# murdock_top_v3.net
KiCad netlist of a schematic drawn in EAGLE
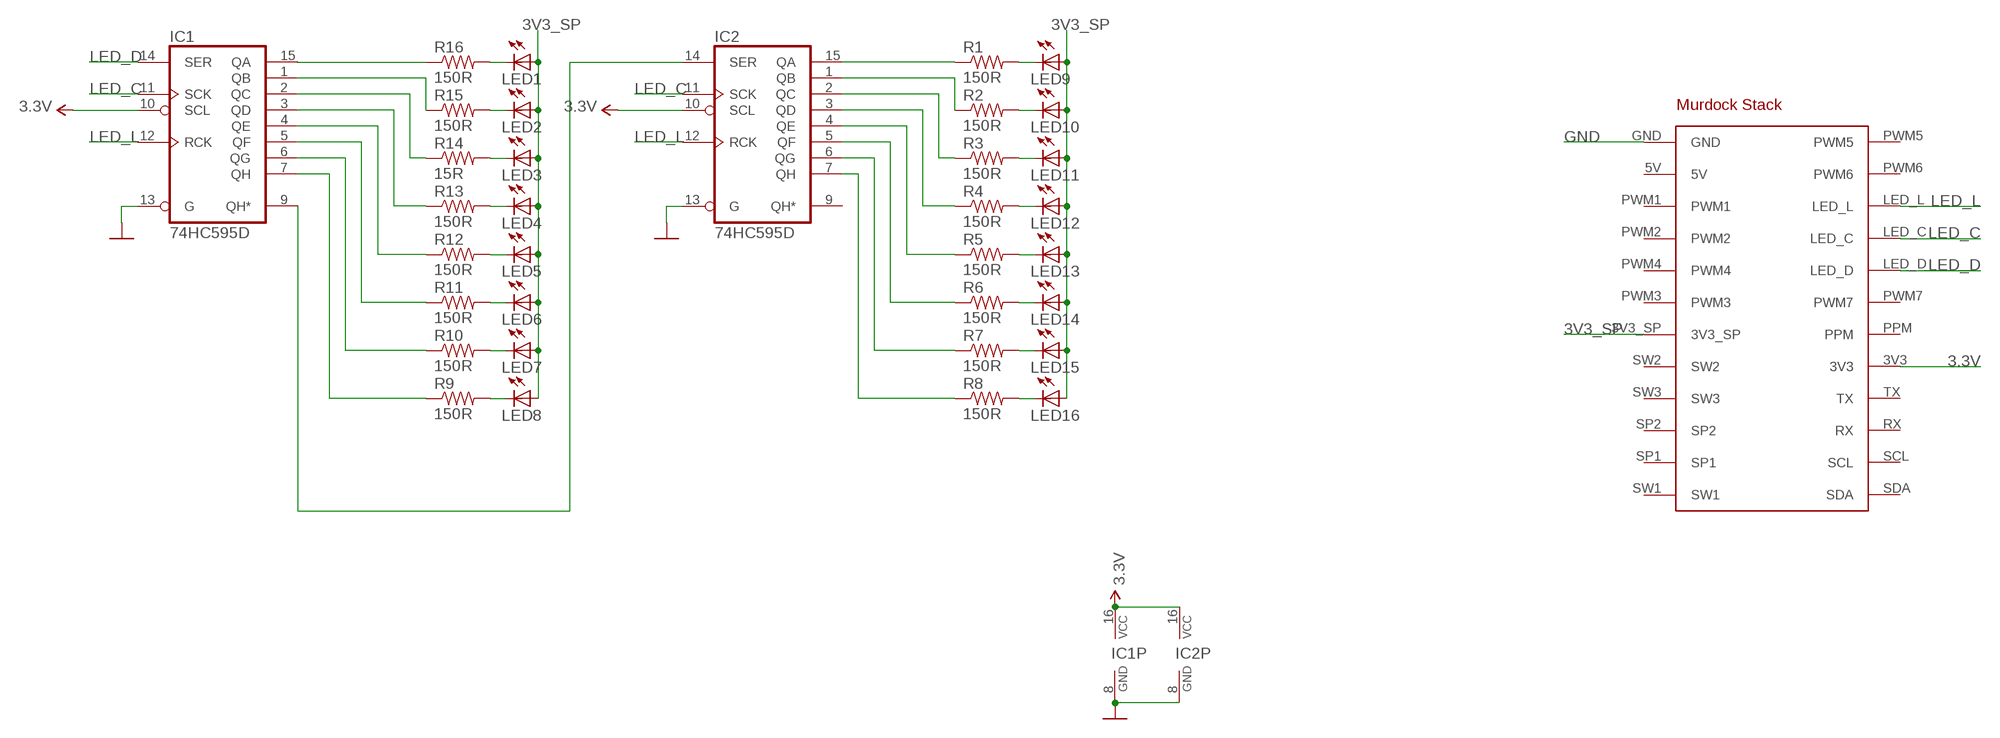
[diagram p0: schematic, sheet 1]

(export (version "E")
  (design (tool "Eeschema 10.0.6"))
  (components
    (comp (ref "IC1")
      (value "74HC595D")
      (footprint "eagle-import:SO16")
      (libsource (lib "eagle-import") (part "74595DHC"))
    )
    (comp (ref "IC2")
      (value "74HC595D")
      (footprint "eagle-import:SO16")
      (libsource (lib "eagle-import") (part "74595DHC"))
    )
    (comp (ref "LED1")
      (value "LGM47K")
      (footprint "eagle-import:LGM47K")
      (libsource (lib "eagle-import") (part "LGM47K"))
    )
    (comp (ref "LED2")
      (value "LGM47K")
      (footprint "eagle-import:LGM47K")
      (libsource (lib "eagle-import") (part "LGM47K"))
    )
    (comp (ref "LED3")
      (value "LGM47K")
      (footprint "eagle-import:LGM47K")
      (libsource (lib "eagle-import") (part "LGM47K"))
    )
    (comp (ref "LED4")
      (value "LGM47K")
      (footprint "eagle-import:LGM47K")
      (libsource (lib "eagle-import") (part "LGM47K"))
    )
    (comp (ref "LED5")
      (value "LGM47K")
      (footprint "eagle-import:LGM47K")
      (libsource (lib "eagle-import") (part "LGM47K"))
    )
    (comp (ref "LED6")
      (value "LGM47K")
      (footprint "eagle-import:LGM47K")
      (libsource (lib "eagle-import") (part "LGM47K"))
    )
    (comp (ref "LED7")
      (value "LGM47K")
      (footprint "eagle-import:LGM47K")
      (libsource (lib "eagle-import") (part "LGM47K"))
    )
    (comp (ref "LED8")
      (value "LGM47K")
      (footprint "eagle-import:LGM47K")
      (libsource (lib "eagle-import") (part "LGM47K"))
    )
    (comp (ref "LED9")
      (value "LGM47K")
      (footprint "eagle-import:LGM47K")
      (libsource (lib "eagle-import") (part "LGM47K"))
    )
    (comp (ref "LED10")
      (value "LGM47K")
      (footprint "eagle-import:LGM47K")
      (libsource (lib "eagle-import") (part "LGM47K"))
    )
    (comp (ref "LED11")
      (value "LGM47K")
      (footprint "eagle-import:LGM47K")
      (libsource (lib "eagle-import") (part "LGM47K"))
    )
    (comp (ref "LED12")
      (value "LGM47K")
      (footprint "eagle-import:LGM47K")
      (libsource (lib "eagle-import") (part "LGM47K"))
    )
    (comp (ref "LED13")
      (value "LGM47K")
      (footprint "eagle-import:LGM47K")
      (libsource (lib "eagle-import") (part "LGM47K"))
    )
    (comp (ref "LED14")
      (value "LGM47K")
      (footprint "eagle-import:LGM47K")
      (libsource (lib "eagle-import") (part "LGM47K"))
    )
    (comp (ref "LED15")
      (value "LGM47K")
      (footprint "eagle-import:LGM47K")
      (libsource (lib "eagle-import") (part "LGM47K"))
    )
    (comp (ref "LED16")
      (value "LGM47K")
      (footprint "eagle-import:LGM47K")
      (libsource (lib "eagle-import") (part "LGM47K"))
    )
    (comp (ref "R1")
      (value "150R")
      (footprint "eagle-import:0402-RES")
      (libsource (lib "eagle-import") (part "RESISTOR0402-RES"))
    )
    (comp (ref "R2")
      (value "150R")
      (footprint "eagle-import:0402-RES")
      (libsource (lib "eagle-import") (part "RESISTOR0402-RES"))
    )
    (comp (ref "R3")
      (value "150R")
      (footprint "eagle-import:0402-RES")
      (libsource (lib "eagle-import") (part "RESISTOR0402-RES"))
    )
    (comp (ref "R4")
      (value "150R")
      (footprint "eagle-import:0402-RES")
      (libsource (lib "eagle-import") (part "RESISTOR0402-RES"))
    )
    (comp (ref "R5")
      (value "150R")
      (footprint "eagle-import:0402-RES")
      (libsource (lib "eagle-import") (part "RESISTOR0402-RES"))
    )
    (comp (ref "R6")
      (value "150R")
      (footprint "eagle-import:0402-RES")
      (libsource (lib "eagle-import") (part "RESISTOR0402-RES"))
    )
    (comp (ref "R7")
      (value "150R")
      (footprint "eagle-import:0402-RES")
      (libsource (lib "eagle-import") (part "RESISTOR0402-RES"))
    )
    (comp (ref "R8")
      (value "150R")
      (footprint "eagle-import:0402-RES")
      (libsource (lib "eagle-import") (part "RESISTOR0402-RES"))
    )
    (comp (ref "R9")
      (value "150R")
      (footprint "eagle-import:0402-RES")
      (libsource (lib "eagle-import") (part "RESISTOR0402-RES"))
    )
    (comp (ref "R10")
      (value "150R")
      (footprint "eagle-import:0402-RES")
      (libsource (lib "eagle-import") (part "RESISTOR0402-RES"))
    )
    (comp (ref "R11")
      (value "150R")
      (footprint "eagle-import:0402-RES")
      (libsource (lib "eagle-import") (part "RESISTOR0402-RES"))
    )
    (comp (ref "R12")
      (value "150R")
      (footprint "eagle-import:0402-RES")
      (libsource (lib "eagle-import") (part "RESISTOR0402-RES"))
    )
    (comp (ref "R13")
      (value "150R")
      (footprint "eagle-import:0402-RES")
      (libsource (lib "eagle-import") (part "RESISTOR0402-RES"))
    )
    (comp (ref "R14")
      (value "15R")
      (footprint "eagle-import:0402-RES")
      (libsource (lib "eagle-import") (part "RESISTOR0402-RES"))
    )
    (comp (ref "R15")
      (value "150R")
      (footprint "eagle-import:0402-RES")
      (libsource (lib "eagle-import") (part "RESISTOR0402-RES"))
    )
    (comp (ref "R16")
      (value "150R")
      (footprint "eagle-import:0402-RES")
      (libsource (lib "eagle-import") (part "RESISTOR0402-RES"))
    )
    (comp (ref "X1")
      (value "MURDOCK_STACK")
      (footprint "eagle-import:MURDOCK_STACK")
      (libsource (lib "eagle-import") (part "MURDOCK_STACK"))
    )
  )
  (nets
    (net (code "1") (name "/3V3_SP") (class "Default")
      (node (ref "LED1") (pin "A") (pinfunction "A_A") (pintype "passive"))
      (node (ref "LED10") (pin "A") (pinfunction "A_A") (pintype "passive"))
      (node (ref "LED11") (pin "A") (pinfunction "A_A") (pintype "passive"))
      (node (ref "LED12") (pin "A") (pinfunction "A_A") (pintype "passive"))
      (node (ref "LED13") (pin "A") (pinfunction "A_A") (pintype "passive"))
      (node (ref "LED14") (pin "A") (pinfunction "A_A") (pintype "passive"))
      (node (ref "LED15") (pin "A") (pinfunction "A_A") (pintype "passive"))
      (node (ref "LED16") (pin "A") (pinfunction "A_A") (pintype "passive"))
      (node (ref "LED2") (pin "A") (pinfunction "A_A") (pintype "passive"))
      (node (ref "LED3") (pin "A") (pinfunction "A_A") (pintype "passive"))
      (node (ref "LED4") (pin "A") (pinfunction "A_A") (pintype "passive"))
      (node (ref "LED5") (pin "A") (pinfunction "A_A") (pintype "passive"))
      (node (ref "LED6") (pin "A") (pinfunction "A_A") (pintype "passive"))
      (node (ref "LED7") (pin "A") (pinfunction "A_A") (pintype "passive"))
      (node (ref "LED8") (pin "A") (pinfunction "A_A") (pintype "passive"))
      (node (ref "LED9") (pin "A") (pinfunction "A_A") (pintype "passive"))
      (node (ref "X1") (pin "3V3_SP") (pinfunction "3V3_SP_3V3_SP") (pintype "bidirectional"))
    )
    (net (code "2") (name "/LED_C") (class "Default")
      (node (ref "IC1") (pin "11") (pinfunction "SCK_11") (pintype "input"))
      (node (ref "IC2") (pin "11") (pinfunction "SCK_11") (pintype "input"))
      (node (ref "X1") (pin "LED_C") (pinfunction "LED_C_LED_C") (pintype "bidirectional"))
    )
    (net (code "3") (name "/LED_D") (class "Default")
      (node (ref "IC1") (pin "14") (pinfunction "SER_14") (pintype "input"))
      (node (ref "X1") (pin "LED_D") (pinfunction "LED_D_LED_D") (pintype "bidirectional"))
    )
    (net (code "4") (name "/LED_L") (class "Default")
      (node (ref "IC1") (pin "12") (pinfunction "RCK_12") (pintype "input"))
      (node (ref "IC2") (pin "12") (pinfunction "RCK_12") (pintype "input"))
      (node (ref "X1") (pin "LED_L") (pinfunction "LED_L_LED_L") (pintype "bidirectional"))
    )
    (net (code "5") (name "3.3V") (class "Default")
      (node (ref "IC1") (pin "10") (pinfunction "SCL_10") (pintype "input"))
      (node (ref "IC1") (pin "16") (pinfunction "VCC_16") (pintype "power_in"))
      (node (ref "IC2") (pin "10") (pinfunction "SCL_10") (pintype "input"))
      (node (ref "IC2") (pin "16") (pinfunction "VCC_16") (pintype "power_in"))
      (node (ref "X1") (pin "3V3") (pinfunction "3V3_3V3") (pintype "bidirectional"))
    )
    (net (code "6") (name "GND") (class "Default")
      (node (ref "IC1") (pin "13") (pinfunction "G_13") (pintype "input"))
      (node (ref "IC1") (pin "8") (pinfunction "GND_8") (pintype "power_in"))
      (node (ref "IC2") (pin "13") (pinfunction "G_13") (pintype "input"))
      (node (ref "IC2") (pin "8") (pinfunction "GND_8") (pintype "power_in"))
      (node (ref "X1") (pin "GND") (pinfunction "GND_GND") (pintype "bidirectional"))
    )
    (net (code "7") (name "Net-(IC1A-QA)") (class "Default")
      (node (ref "IC1") (pin "15") (pinfunction "QA_15") (pintype "tri_state"))
      (node (ref "R16") (pin "1") (pinfunction "1_1") (pintype "passive"))
    )
    (net (code "8") (name "Net-(IC1A-QB)") (class "Default")
      (node (ref "IC1") (pin "1") (pinfunction "QB_1") (pintype "tri_state"))
      (node (ref "R15") (pin "1") (pinfunction "1_1") (pintype "passive"))
    )
    (net (code "9") (name "Net-(IC1A-QC)") (class "Default")
      (node (ref "IC1") (pin "2") (pinfunction "QC_2") (pintype "tri_state"))
      (node (ref "R14") (pin "1") (pinfunction "1_1") (pintype "passive"))
    )
    (net (code "10") (name "Net-(IC1A-QD)") (class "Default")
      (node (ref "IC1") (pin "3") (pinfunction "QD_3") (pintype "tri_state"))
      (node (ref "R13") (pin "1") (pinfunction "1_1") (pintype "passive"))
    )
    (net (code "11") (name "Net-(IC1A-QE)") (class "Default")
      (node (ref "IC1") (pin "4") (pinfunction "QE_4") (pintype "tri_state"))
      (node (ref "R12") (pin "1") (pinfunction "1_1") (pintype "passive"))
    )
    (net (code "12") (name "Net-(IC1A-QF)") (class "Default")
      (node (ref "IC1") (pin "5") (pinfunction "QF_5") (pintype "tri_state"))
      (node (ref "R11") (pin "1") (pinfunction "1_1") (pintype "passive"))
    )
    (net (code "13") (name "Net-(IC1A-QG)") (class "Default")
      (node (ref "IC1") (pin "6") (pinfunction "QG_6") (pintype "tri_state"))
      (node (ref "R10") (pin "1") (pinfunction "1_1") (pintype "passive"))
    )
    (net (code "14") (name "Net-(IC1A-QH)") (class "Default")
      (node (ref "IC1") (pin "7") (pinfunction "QH_7") (pintype "tri_state"))
      (node (ref "R9") (pin "1") (pinfunction "1_1") (pintype "passive"))
    )
    (net (code "15") (name "Net-(IC1A-QH*)") (class "Default")
      (node (ref "IC1") (pin "9") (pinfunction "QH*_9") (pintype "tri_state"))
      (node (ref "IC2") (pin "14") (pinfunction "SER_14") (pintype "input"))
    )
    (net (code "16") (name "Net-(IC2A-QA)") (class "Default")
      (node (ref "IC2") (pin "15") (pinfunction "QA_15") (pintype "tri_state"))
      (node (ref "R1") (pin "1") (pinfunction "1_1") (pintype "passive"))
    )
    (net (code "17") (name "Net-(IC2A-QB)") (class "Default")
      (node (ref "IC2") (pin "1") (pinfunction "QB_1") (pintype "tri_state"))
      (node (ref "R2") (pin "1") (pinfunction "1_1") (pintype "passive"))
    )
    (net (code "18") (name "Net-(IC2A-QC)") (class "Default")
      (node (ref "IC2") (pin "2") (pinfunction "QC_2") (pintype "tri_state"))
      (node (ref "R3") (pin "1") (pinfunction "1_1") (pintype "passive"))
    )
    (net (code "19") (name "Net-(IC2A-QD)") (class "Default")
      (node (ref "IC2") (pin "3") (pinfunction "QD_3") (pintype "tri_state"))
      (node (ref "R4") (pin "1") (pinfunction "1_1") (pintype "passive"))
    )
    (net (code "20") (name "Net-(IC2A-QE)") (class "Default")
      (node (ref "IC2") (pin "4") (pinfunction "QE_4") (pintype "tri_state"))
      (node (ref "R5") (pin "1") (pinfunction "1_1") (pintype "passive"))
    )
    (net (code "21") (name "Net-(IC2A-QF)") (class "Default")
      (node (ref "IC2") (pin "5") (pinfunction "QF_5") (pintype "tri_state"))
      (node (ref "R6") (pin "1") (pinfunction "1_1") (pintype "passive"))
    )
    (net (code "22") (name "Net-(IC2A-QG)") (class "Default")
      (node (ref "IC2") (pin "6") (pinfunction "QG_6") (pintype "tri_state"))
      (node (ref "R7") (pin "1") (pinfunction "1_1") (pintype "passive"))
    )
    (net (code "23") (name "Net-(IC2A-QH)") (class "Default")
      (node (ref "IC2") (pin "7") (pinfunction "QH_7") (pintype "tri_state"))
      (node (ref "R8") (pin "1") (pinfunction "1_1") (pintype "passive"))
    )
    (net (code "24") (name "Net-(LED1-C)") (class "Default")
      (node (ref "LED1") (pin "K") (pinfunction "C_K") (pintype "passive"))
      (node (ref "R16") (pin "2") (pinfunction "2_2") (pintype "passive"))
    )
    (net (code "25") (name "Net-(LED2-C)") (class "Default")
      (node (ref "LED2") (pin "K") (pinfunction "C_K") (pintype "passive"))
      (node (ref "R15") (pin "2") (pinfunction "2_2") (pintype "passive"))
    )
    (net (code "26") (name "Net-(LED3-C)") (class "Default")
      (node (ref "LED3") (pin "K") (pinfunction "C_K") (pintype "passive"))
      (node (ref "R14") (pin "2") (pinfunction "2_2") (pintype "passive"))
    )
    (net (code "27") (name "Net-(LED4-C)") (class "Default")
      (node (ref "LED4") (pin "K") (pinfunction "C_K") (pintype "passive"))
      (node (ref "R13") (pin "2") (pinfunction "2_2") (pintype "passive"))
    )
    (net (code "28") (name "Net-(LED5-C)") (class "Default")
      (node (ref "LED5") (pin "K") (pinfunction "C_K") (pintype "passive"))
      (node (ref "R12") (pin "2") (pinfunction "2_2") (pintype "passive"))
    )
    (net (code "29") (name "Net-(LED6-C)") (class "Default")
      (node (ref "LED6") (pin "K") (pinfunction "C_K") (pintype "passive"))
      (node (ref "R11") (pin "2") (pinfunction "2_2") (pintype "passive"))
    )
    (net (code "30") (name "Net-(LED7-C)") (class "Default")
      (node (ref "LED7") (pin "K") (pinfunction "C_K") (pintype "passive"))
      (node (ref "R10") (pin "2") (pinfunction "2_2") (pintype "passive"))
    )
    (net (code "31") (name "Net-(LED8-C)") (class "Default")
      (node (ref "LED8") (pin "K") (pinfunction "C_K") (pintype "passive"))
      (node (ref "R9") (pin "2") (pinfunction "2_2") (pintype "passive"))
    )
    (net (code "32") (name "Net-(LED9-C)") (class "Default")
      (node (ref "LED9") (pin "K") (pinfunction "C_K") (pintype "passive"))
      (node (ref "R1") (pin "2") (pinfunction "2_2") (pintype "passive"))
    )
    (net (code "33") (name "Net-(LED10-C)") (class "Default")
      (node (ref "LED10") (pin "K") (pinfunction "C_K") (pintype "passive"))
      (node (ref "R2") (pin "2") (pinfunction "2_2") (pintype "passive"))
    )
    (net (code "34") (name "Net-(LED11-C)") (class "Default")
      (node (ref "LED11") (pin "K") (pinfunction "C_K") (pintype "passive"))
      (node (ref "R3") (pin "2") (pinfunction "2_2") (pintype "passive"))
    )
    (net (code "35") (name "Net-(LED12-C)") (class "Default")
      (node (ref "LED12") (pin "K") (pinfunction "C_K") (pintype "passive"))
      (node (ref "R4") (pin "2") (pinfunction "2_2") (pintype "passive"))
    )
    (net (code "36") (name "Net-(LED13-C)") (class "Default")
      (node (ref "LED13") (pin "K") (pinfunction "C_K") (pintype "passive"))
      (node (ref "R5") (pin "2") (pinfunction "2_2") (pintype "passive"))
    )
    (net (code "37") (name "Net-(LED14-C)") (class "Default")
      (node (ref "LED14") (pin "K") (pinfunction "C_K") (pintype "passive"))
      (node (ref "R6") (pin "2") (pinfunction "2_2") (pintype "passive"))
    )
    (net (code "38") (name "Net-(LED15-C)") (class "Default")
      (node (ref "LED15") (pin "K") (pinfunction "C_K") (pintype "passive"))
      (node (ref "R7") (pin "2") (pinfunction "2_2") (pintype "passive"))
    )
    (net (code "39") (name "Net-(LED16-C)") (class "Default")
      (node (ref "LED16") (pin "K") (pinfunction "C_K") (pintype "passive"))
      (node (ref "R8") (pin "2") (pinfunction "2_2") (pintype "passive"))
    )
    (net (code "40") (name "unconnected-(IC2A-QH*-Pad9)") (class "Default")
      (node (ref "IC2") (pin "9") (pinfunction "QH*_9") (pintype "tri_state"))
    )
    (net (code "41") (name "unconnected-(X1-Pad5V)") (class "Default")
      (node (ref "X1") (pin "5V") (pinfunction "5V_5V") (pintype "bidirectional"))
    )
    (net (code "42") (name "unconnected-(X1-PadPPM)") (class "Default")
      (node (ref "X1") (pin "PPM") (pinfunction "PPM_PPM") (pintype "bidirectional"))
    )
    (net (code "43") (name "unconnected-(X1-PadPWM1)") (class "Default")
      (node (ref "X1") (pin "PWM1") (pinfunction "PWM1_PWM1") (pintype "bidirectional"))
    )
    (net (code "44") (name "unconnected-(X1-PadPWM2)") (class "Default")
      (node (ref "X1") (pin "PWM2") (pinfunction "PWM2_PWM2") (pintype "bidirectional"))
    )
    (net (code "45") (name "unconnected-(X1-PadPWM3)") (class "Default")
      (node (ref "X1") (pin "PWM3") (pinfunction "PWM3_PWM3") (pintype "bidirectional"))
    )
    (net (code "46") (name "unconnected-(X1-PadPWM4)") (class "Default")
      (node (ref "X1") (pin "PWM4") (pinfunction "PWM4_PWM4") (pintype "bidirectional"))
    )
    (net (code "47") (name "unconnected-(X1-PadPWM5)") (class "Default")
      (node (ref "X1") (pin "PWM5") (pinfunction "PWM5_PWM5") (pintype "bidirectional"))
    )
    (net (code "48") (name "unconnected-(X1-PadPWM6)") (class "Default")
      (node (ref "X1") (pin "PWM6") (pinfunction "PWM6_PWM6") (pintype "bidirectional"))
    )
    (net (code "49") (name "unconnected-(X1-PadPWM7)") (class "Default")
      (node (ref "X1") (pin "PWM7") (pinfunction "PWM7_PWM7") (pintype "bidirectional"))
    )
    (net (code "50") (name "unconnected-(X1-PadRX)") (class "Default")
      (node (ref "X1") (pin "RX") (pinfunction "RX_RX") (pintype "bidirectional"))
    )
    (net (code "51") (name "unconnected-(X1-PadSCL)") (class "Default")
      (node (ref "X1") (pin "SCL") (pinfunction "SCL_SCL") (pintype "bidirectional"))
    )
    (net (code "52") (name "unconnected-(X1-PadSDA)") (class "Default")
      (node (ref "X1") (pin "SDA") (pinfunction "SDA_SDA") (pintype "bidirectional"))
    )
    (net (code "53") (name "unconnected-(X1-PadSP1)") (class "Default")
      (node (ref "X1") (pin "SP1") (pinfunction "SP1_SP1") (pintype "bidirectional"))
    )
    (net (code "54") (name "unconnected-(X1-PadSP2)") (class "Default")
      (node (ref "X1") (pin "SP2") (pinfunction "SP2_SP2") (pintype "bidirectional"))
    )
    (net (code "55") (name "unconnected-(X1-PadSW1)") (class "Default")
      (node (ref "X1") (pin "SW1") (pinfunction "SW1_SW1") (pintype "bidirectional"))
    )
    (net (code "56") (name "unconnected-(X1-PadSW2)") (class "Default")
      (node (ref "X1") (pin "SW2") (pinfunction "SW2_SW2") (pintype "bidirectional"))
    )
    (net (code "57") (name "unconnected-(X1-PadSW3)") (class "Default")
      (node (ref "X1") (pin "SW3") (pinfunction "SW3_SW3") (pintype "bidirectional"))
    )
    (net (code "58") (name "unconnected-(X1-PadTX)") (class "Default")
      (node (ref "X1") (pin "TX") (pinfunction "TX_TX") (pintype "bidirectional"))
    )
  )
)
